# 03_Power_DC.net
KiCad netlist of a schematic drawn in Altium Designer
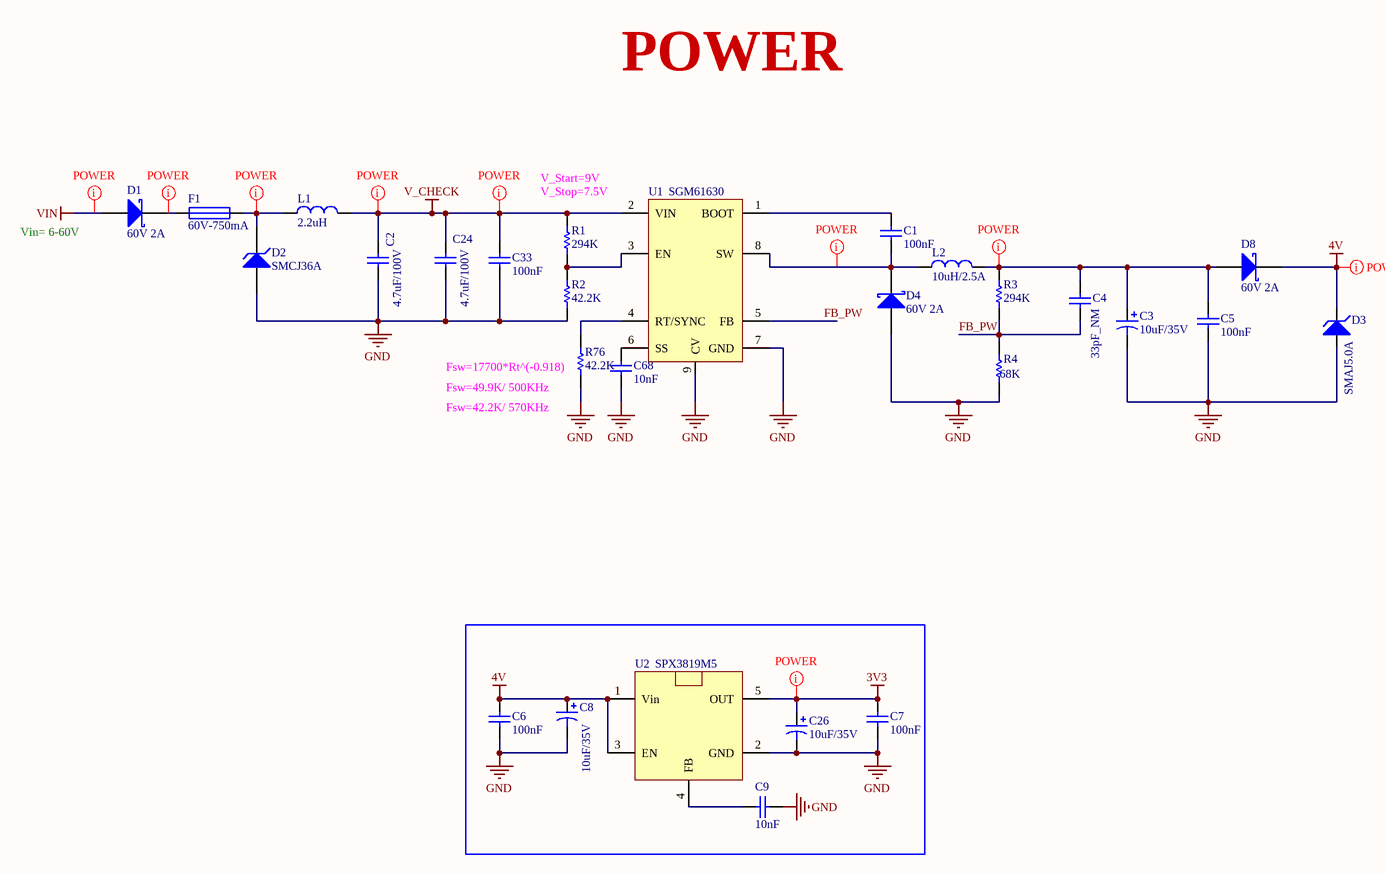
[diagram p0: 03 Power DC.SchDoc]

(export (version "E")
  (design (tool "Eeschema 10.0.6"))
  (components
    (comp (ref "C1")
      (value "100nF")
      (footprint "0603 - C")
      (description "CAP CER 100nF 50V C0G/NP0 0603 ±5%")
      (fields (field (name "VOLTAGE") "50V") (field (name "MPN") "CL10C104JB8NNNC"))
      (libsource (lib "Library_Chip") (part "Cap 0603 100nF"))
    )
    (comp (ref "C2")
      (value "4.7uF/100V")
      (footprint "1210 - C")
      (description "CAP CER 4.7UF 100V X5R 1210")
      (fields (field (name "MFR") "Taiyo Yuden") (field (name "MPN") "HMK325BJ475KM-PE"))
      (libsource (lib "Library_Chip") (part "Cap 1210 4.7uF"))
    )
    (comp (ref "C3")
      (value "10uF/35V")
      (footprint "CAP_ALUM_SMD_5054_TYPE_C")
      (description "CAP ALUM 100UF 20% 6.3V SMD 5x5.4mm")
      (fields (field (name "MPN") "UWT1V100MCL1GB") (field (name "MFR") "Nichicon"))
      (libsource (lib "Library_Chip") (part "Cap Alu 10uF/35V"))
    )
    (comp (ref "C4")
      (value "33pF_NM")
      (footprint "0603 - C")
      (description "CAP CER 33PF 50V C0G 0603")
      (fields (field (name "MFR") "Yageo") (field (name "MPN") "AC0603FRNPO9BN330"))
      (libsource (lib "Library_Chip") (part "Cap 0603 33pF"))
    )
    (comp (ref "C5")
      (value "100nF")
      (footprint "0603 - C")
      (description "CAP CER 100nF 50V C0G/NP0 0603 ±5%")
      (fields (field (name "VOLTAGE") "50V") (field (name "MPN") "CL10C104JB8NNNC"))
      (libsource (lib "Library_Chip") (part "Cap 0603 100nF"))
    )
    (comp (ref "C6")
      (value "100nF")
      (footprint "0603 - C")
      (description "CAP CER 100nF 50V C0G/NP0 0603 ±5%")
      (fields (field (name "VOLTAGE") "50V") (field (name "MPN") "CL10C104JB8NNNC"))
      (libsource (lib "Library_Chip") (part "Cap 0603 100nF"))
    )
    (comp (ref "C7")
      (value "100nF")
      (footprint "0603 - C")
      (description "CAP CER 100nF 50V C0G/NP0 0603 ±5%")
      (fields (field (name "VOLTAGE") "50V") (field (name "MPN") "CL10C104JB8NNNC"))
      (libsource (lib "Library_Chip") (part "Cap 0603 100nF"))
    )
    (comp (ref "C8")
      (value "10uF/35V")
      (footprint "CAP_ALUM_SMD_5054_TYPE_C")
      (description "CAP ALUM 10UF 20% 35V SMD 5x5.4mm")
      (fields (field (name "MPN") "UWT1V100MCL1GB") (field (name "MFR") "Nichicon"))
      (libsource (lib "Library_Chip") (part "Cap Alu 10uF/35V"))
    )
    (comp (ref "C9")
      (value "10nF")
      (footprint "0603 - C")
      (description "CAP CER 10nF 50V C0G/NP0 0603")
      (fields (field (name "MPN") "CL10C103JB8NNNC") (field (name "MFR") "SAMSUNG"))
      (libsource (lib "Library_Chip") (part "Cap 0603 10nF"))
    )
    (comp (ref "C24")
      (value "4.7uF/100V")
      (footprint "1210 - C")
      (description "CAP CER 4.7UF 100V X5R 1210")
      (fields (field (name "MFR") "Taiyo Yuden") (field (name "MPN") "HMK325BJ475KM-PE"))
      (libsource (lib "Library_Chip") (part "Cap 1210 4.7uF"))
    )
    (comp (ref "C26")
      (value "10uF/35V")
      (footprint "CAP_ALUM_SMD_5054_TYPE_C")
      (description "CAP ALUM 10UF 20% 35V SMD 5x5.4mm")
      (fields (field (name "MPN") "UWT1V100MCL1GB") (field (name "MFR") "Nichicon"))
      (libsource (lib "Library_Chip") (part "Cap Alu 10uF/35V"))
    )
    (comp (ref "C33")
      (value "100nF")
      (footprint "0603 - C")
      (description "CAP CER 100nF 50V C0G/NP0 0603 ±5%")
      (fields (field (name "VOLTAGE") "50V") (field (name "MPN") "CL10C104JB8NNNC"))
      (libsource (lib "Library_Chip") (part "Cap 0603 100nF"))
    )
    (comp (ref "C68")
      (value "10nF")
      (footprint "0603 - C")
      (description "CAP CER 10nF 50V C0G/NP0 0603")
      (fields (field (name "MPN") "CL10C103JB8NNNC") (field (name "MFR") "SAMSUNG"))
      (libsource (lib "Library_Chip") (part "Cap 0603 10nF"))
    )
    (comp (ref "D1")
      (value "60V 2A")
      (footprint "SOD-123")
      (description "DIODE SCHOTTKY 60V 2A SOD123W")
      (fields (field (name "MPN") "PMEG6020ER,115") (field (name "MFR") "NXP"))
      (libsource (lib "Library_Chip") (part "Diode PMEG6020ER"))
    )
    (comp (ref "D2")
      (value "SMCJ36A")
      (footprint "DIODE - SMC")
      (description "TVS DIODE 36V 58.1V DO214AB")
      (fields (field (name "MFR") "Vishay") (field (name "MPN") "SMCJ36A-E3/9AT"))
      (libsource (lib "Library_Chip") (part "Diode SMCJ36A"))
    )
    (comp (ref "D3")
      (value "SMAJ5.0A")
      (footprint "Diode - SMA")
      (description "TVS DIODE 5VWM 9.2VC SMA")
      (fields (field (name "MFR") "Littelfuse Inc."))
      (libsource (lib "Library_Chip") (part "Diode SMAJ5.0A"))
    )
    (comp (ref "D4")
      (value "60V 2A")
      (footprint "SOD-123")
      (description "DIODE SCHOTTKY 60V 2A SOD123W")
      (fields (field (name "MPN") "PMEG6020ER,115") (field (name "MFR") "NXP"))
      (libsource (lib "Library_Chip") (part "Diode PMEG6020ER"))
    )
    (comp (ref "D8")
      (value "60V 2A")
      (footprint "SOD-123")
      (description "DIODE SCHOTTKY 60V 2A SOD123W")
      (fields (field (name "MPN") "PMEG6020ER,115") (field (name "MFR") "NXP"))
      (libsource (lib "Library_Chip") (part "Diode PMEG6020ER"))
    )
    (comp (ref "F1")
      (value "60V-750mA")
      (footprint "2016 - Fuse")
      (description "PTC RESET FUSE 60V 750MA 2016")
      (fields (field (name "MFR") "Littelfuse Inc.") (field (name "MPN") "2016L075/60MR"))
      (libsource (lib "Library_Chip") (part "Fuse 60V - 750mA"))
    )
    (comp (ref "L1")
      (value "2.2uH")
      (footprint "1210 - L")
      (description "FIXED IND 2.2UH 1.6A 76 MOHM SMD")
      (fields (field (name "MPN") "LQH32PN2R2NN0") (field (name "MFR") "Murata"))
      (libsource (lib "Library_Chip") (part "Inductor 3225 2.2uH"))
    )
    (comp (ref "L2")
      (value "10uH/2.5A")
      (footprint "INDUCTOR-5D28")
      (description "FIXED IND 10UH 2.5A 61.1MOHM SMD")
      (fields (field (name "MFR") "Taiyo Yuden") (field (name "MPN") "NR6045T100M"))
      (libsource (lib "Library_Chip") (part "Inductor 10uH 2.5A"))
    )
    (comp (ref "R1")
      (value "294K")
      (footprint "0603 - R")
      (description "RES SMD 294K OHM 1% 1/10W 0603")
      (fields (field (name "MFR") "Yageo") (field (name "MPN") "RC0603FR-07294KL"))
      (libsource (lib "Library_Chip") (part "Res 0603 294K"))
    )
    (comp (ref "R2")
      (value "42.2K")
      (footprint "0603 - R")
      (description "RES SMD 42K2 OHM 1% 1/10W 0603")
      (fields (field (name "MFR") "Yageo") (field (name "MPN") "RC0603FR-0742K2L"))
      (libsource (lib "Library_Chip") (part "Res 0603 42.2K"))
    )
    (comp (ref "R3")
      (value "294K")
      (footprint "0603 - R")
      (description "RES SMD 294K OHM 1% 1/10W 0603")
      (fields (field (name "MFR") "Yageo") (field (name "MPN") "RC0603FR-07294KL"))
      (libsource (lib "Library_Chip") (part "Res 0603 294K"))
    )
    (comp (ref "R4")
      (value "68K")
      (footprint "0603 - R")
      (description "RES SMD 68K OHM 1% 1/10W 0603")
      (fields (field (name "MFR") "Yageo") (field (name "MPN") "RC0603FR-0768KL"))
      (libsource (lib "Library_Chip") (part "Res 0603 68K"))
    )
    (comp (ref "R76")
      (value "42.2K")
      (footprint "0603 - R")
      (description "RES SMD 42K2 OHM 1% 1/10W 0603")
      (fields (field (name "MFR") "Yageo") (field (name "MPN") "RC0603FR-0742K2L"))
      (libsource (lib "Library_Chip") (part "Res 0603 42.2K"))
    )
    (comp (ref "U1")
      (value "SGM61630")
      (footprint "SOIC8 - POWER")
      (fields (field (name "MPN") "SGM61630AXPS8G/TR") (field (name "MFR") "SGMICRO"))
      (libsource (lib "Library_IC") (part "SGM61630"))
    )
    (comp (ref "U2")
      (value "SPX3819M5")
      (footprint "SOT23-5")
      (description "IC REG LINEAR 3.3V 500MA SOT23-5")
      (fields (field (name "MFR") "MaxLinear") (field (name "MPN") "SPX3819M5-L-3-3/TR"))
      (libsource (lib "Library_IC") (part "SPX3819M5-L-3-3/TR"))
    )
  )
  (nets
    (net (code "1") (name "/FB_PW") (class "Default")
      (node (ref "C4") (pin "1") (pinfunction "1_1") (pintype "passive"))
      (node (ref "R3") (pin "1") (pinfunction "1_1") (pintype "passive"))
      (node (ref "R4") (pin "2") (pinfunction "2_2") (pintype "passive"))
      (node (ref "U1") (pin "5") (pinfunction "FB_5") (pintype "passive"))
    )
    (net (code "2") (name "3V3") (class "Default")
      (node (ref "C26") (pin "1") (pinfunction "1_1") (pintype "passive"))
      (node (ref "C7") (pin "2") (pinfunction "2_2") (pintype "passive"))
      (node (ref "U2") (pin "5") (pinfunction "OUT_5") (pintype "passive"))
    )
    (net (code "3") (name "4V") (class "Default")
      (node (ref "C6") (pin "2") (pinfunction "2_2") (pintype "passive"))
      (node (ref "C8") (pin "1") (pinfunction "1_1") (pintype "passive"))
      (node (ref "D3") (pin "2") (pinfunction "K_2") (pintype "passive"))
      (node (ref "D8") (pin "2") (pinfunction "K_2") (pintype "passive"))
      (node (ref "U2") (pin "1") (pinfunction "Vin_1") (pintype "passive"))
      (node (ref "U2") (pin "3") (pinfunction "EN_3") (pintype "passive"))
    )
    (net (code "4") (name "GND") (class "Default")
      (node (ref "C2") (pin "1") (pinfunction "1_1") (pintype "passive"))
      (node (ref "C24") (pin "1") (pinfunction "1_1") (pintype "passive"))
      (node (ref "C26") (pin "2") (pinfunction "2_2") (pintype "passive"))
      (node (ref "C3") (pin "2") (pinfunction "2_2") (pintype "passive"))
      (node (ref "C33") (pin "1") (pinfunction "1_1") (pintype "passive"))
      (node (ref "C5") (pin "1") (pinfunction "1_1") (pintype "passive"))
      (node (ref "C6") (pin "1") (pinfunction "1_1") (pintype "passive"))
      (node (ref "C68") (pin "1") (pinfunction "1_1") (pintype "passive"))
      (node (ref "C7") (pin "1") (pinfunction "1_1") (pintype "passive"))
      (node (ref "C8") (pin "2") (pinfunction "2_2") (pintype "passive"))
      (node (ref "C9") (pin "2") (pinfunction "2_2") (pintype "passive"))
      (node (ref "D2") (pin "1") (pinfunction "A_1") (pintype "passive"))
      (node (ref "D3") (pin "1") (pinfunction "A_1") (pintype "passive"))
      (node (ref "D4") (pin "1") (pinfunction "A_1") (pintype "passive"))
      (node (ref "R2") (pin "1") (pinfunction "1_1") (pintype "passive"))
      (node (ref "R4") (pin "1") (pinfunction "1_1") (pintype "passive"))
      (node (ref "R76") (pin "1") (pinfunction "1_1") (pintype "passive"))
      (node (ref "U1") (pin "7") (pinfunction "GND_7") (pintype "passive"))
      (node (ref "U1") (pin "9") (pinfunction "CV_9") (pintype "passive"))
      (node (ref "U2") (pin "2") (pinfunction "GND_2") (pintype "passive"))
    )
    (net (code "5") (name "Net-(D1-K)") (class "Default")
      (node (ref "D1") (pin "2") (pinfunction "K_2") (pintype "passive"))
      (node (ref "F1") (pin "1") (pinfunction "1_1") (pintype "passive"))
    )
    (net (code "6") (name "Net-(D2-K)") (class "Default")
      (node (ref "D2") (pin "2") (pinfunction "K_2") (pintype "passive"))
      (node (ref "F1") (pin "2") (pinfunction "2_2") (pintype "passive"))
      (node (ref "L1") (pin "1") (pinfunction "1_1") (pintype "passive"))
    )
    (net (code "7") (name "Net-(D4-K)") (class "Default")
      (node (ref "C1") (pin "2") (pinfunction "2_2") (pintype "passive"))
      (node (ref "D4") (pin "2") (pinfunction "K_2") (pintype "passive"))
      (node (ref "L2") (pin "1") (pinfunction "1_1") (pintype "passive"))
      (node (ref "U1") (pin "8") (pinfunction "SW_8") (pintype "passive"))
    )
    (net (code "8") (name "Net-(D8-A)") (class "Default")
      (node (ref "C3") (pin "1") (pinfunction "1_1") (pintype "passive"))
      (node (ref "C4") (pin "2") (pinfunction "2_2") (pintype "passive"))
      (node (ref "C5") (pin "2") (pinfunction "2_2") (pintype "passive"))
      (node (ref "D8") (pin "1") (pinfunction "A_1") (pintype "passive"))
      (node (ref "L2") (pin "2") (pinfunction "2_2") (pintype "passive"))
      (node (ref "R3") (pin "2") (pinfunction "2_2") (pintype "passive"))
    )
    (net (code "9") (name "Net-(U1-BOOT)") (class "Default")
      (node (ref "C1") (pin "1") (pinfunction "1_1") (pintype "passive"))
      (node (ref "U1") (pin "1") (pinfunction "BOOT_1") (pintype "passive"))
    )
    (net (code "10") (name "Net-(U1-EN)") (class "Default")
      (node (ref "R1") (pin "1") (pinfunction "1_1") (pintype "passive"))
      (node (ref "R2") (pin "2") (pinfunction "2_2") (pintype "passive"))
      (node (ref "U1") (pin "3") (pinfunction "EN_3") (pintype "passive"))
    )
    (net (code "11") (name "Net-(U1-RT{slash}SYNC)") (class "Default")
      (node (ref "R76") (pin "2") (pinfunction "2_2") (pintype "passive"))
      (node (ref "U1") (pin "4") (pinfunction "RT/SYNC_4") (pintype "passive"))
    )
    (net (code "12") (name "Net-(U1-SS)") (class "Default")
      (node (ref "C68") (pin "2") (pinfunction "2_2") (pintype "passive"))
      (node (ref "U1") (pin "6") (pinfunction "SS_6") (pintype "passive"))
    )
    (net (code "13") (name "Net-(U2-FB)") (class "Default")
      (node (ref "C9") (pin "1") (pinfunction "1_1") (pintype "passive"))
      (node (ref "U2") (pin "4") (pinfunction "FB_4") (pintype "open_collector"))
    )
    (net (code "14") (name "VIN") (class "Default")
      (node (ref "D1") (pin "1") (pinfunction "A_1") (pintype "passive"))
    )
    (net (code "15") (name "V_CHECK") (class "Default")
      (node (ref "C2") (pin "2") (pinfunction "2_2") (pintype "passive"))
      (node (ref "C24") (pin "2") (pinfunction "2_2") (pintype "passive"))
      (node (ref "C33") (pin "2") (pinfunction "2_2") (pintype "passive"))
      (node (ref "L1") (pin "2") (pinfunction "2_2") (pintype "passive"))
      (node (ref "R1") (pin "2") (pinfunction "2_2") (pintype "passive"))
      (node (ref "U1") (pin "2") (pinfunction "VIN_2") (pintype "passive"))
    )
    (net (code "16") (name "unconnected-(U2-NC-Pad4)") (class "Default")
      (node (ref "U2") (pin "4") (pinfunction "NC_4") (pintype "passive"))
    )
  )
)
